# LogicBoard.net
KiCad netlist of a schematic drawn in EAGLE
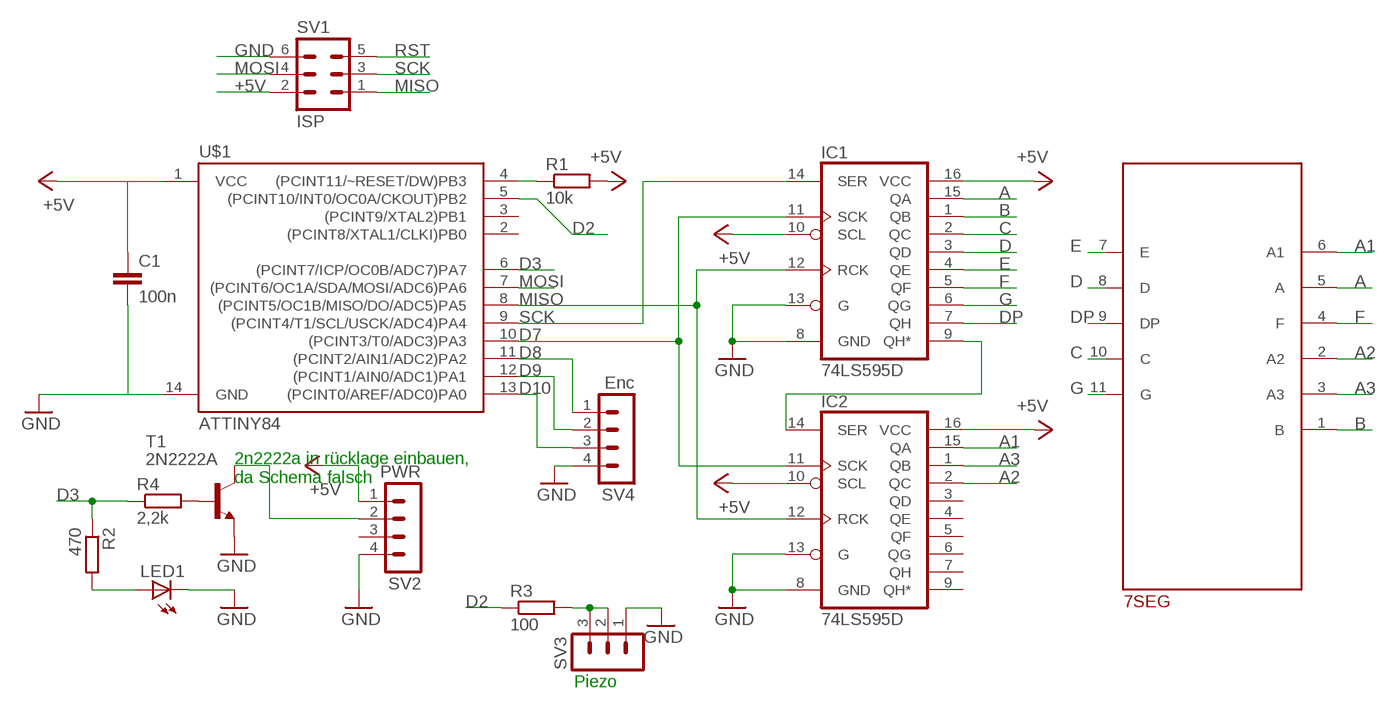
[diagram p0: schematic, sheet 1]

(export (version "E")
  (design (tool "Eeschema 10.0.6"))
  (components
    (comp (ref "7SEG")
      (value "TOT4301TOT-4301FG1")
      (footprint "eagle-import:TOT4301")
      (libsource (lib "eagle-import") (part "TOT4301TOT-4301FG1"))
    )
    (comp (ref "C1")
      (value "100n")
      (footprint "eagle-import:C0805")
      (libsource (lib "eagle-import") (part "C-EUC0805"))
    )
    (comp (ref "IC1")
      (value "74LS595D")
      (footprint "eagle-import:SO16")
      (libsource (lib "eagle-import") (part "74595DLS"))
    )
    (comp (ref "IC2")
      (value "74LS595D")
      (footprint "eagle-import:SO16")
      (libsource (lib "eagle-import") (part "74595DLS"))
    )
    (comp (ref "LED1")
      (value "LED5MM")
      (footprint "eagle-import:LED5MM")
      (libsource (lib "eagle-import") (part "LED5MM"))
    )
    (comp (ref "R1")
      (value "10k")
      (footprint "eagle-import:M0805")
      (libsource (lib "eagle-import") (part "R-EU_M0805"))
    )
    (comp (ref "R2")
      (value "470")
      (footprint "eagle-import:M0805")
      (libsource (lib "eagle-import") (part "R-EU_M0805"))
    )
    (comp (ref "R3")
      (value "100")
      (footprint "eagle-import:M0805")
      (libsource (lib "eagle-import") (part "R-EU_M0805"))
    )
    (comp (ref "R4")
      (value "2,2k")
      (footprint "eagle-import:M0805")
      (libsource (lib "eagle-import") (part "R-EU_M0805"))
    )
    (comp (ref "SV1")
      (value "ISP")
      (footprint "eagle-import:MA03-2")
      (libsource (lib "eagle-import") (part "MA03-2"))
    )
    (comp (ref "SV2")
      (value "PWR")
      (footprint "eagle-import:MA04-1")
      (libsource (lib "eagle-import") (part "MA04-1"))
    )
    (comp (ref "SV3")
      (value "MA03-1")
      (footprint "eagle-import:MA03-1")
      (libsource (lib "eagle-import") (part "MA03-1"))
    )
    (comp (ref "SV4")
      (value "Enc")
      (footprint "eagle-import:MA04-1")
      (libsource (lib "eagle-import") (part "MA04-1"))
    )
    (comp (ref "T1")
      (value "2N2222A")
      (footprint "eagle-import:SOT23-EBC")
      (libsource (lib "eagle-import") (part "-NPN-SOT23-EBC"))
    )
    (comp (ref "U$1")
      (value "ATTINY84")
      (footprint "eagle-import:SO14")
      (libsource (lib "eagle-import") (part "ATTINY84"))
    )
  )
  (nets
    (net (code "1") (name "+5V") (class "Default")
      (node (ref "C1") (pin "1") (pinfunction "1_1") (pintype "passive"))
      (node (ref "IC1") (pin "10") (pinfunction "SCL_10") (pintype "input"))
      (node (ref "IC1") (pin "16") (pinfunction "VCC_16") (pintype "power_in"))
      (node (ref "IC2") (pin "10") (pinfunction "SCL_10") (pintype "input"))
      (node (ref "IC2") (pin "16") (pinfunction "VCC_16") (pintype "power_in"))
      (node (ref "R1") (pin "2") (pinfunction "2_2") (pintype "passive"))
      (node (ref "SV1") (pin "2") (pinfunction "2_2") (pintype "passive"))
      (node (ref "SV2") (pin "1") (pinfunction "1_1") (pintype "passive"))
      (node (ref "U$1") (pin "1") (pinfunction "VCC_1") (pintype "bidirectional"))
    )
    (net (code "2") (name "/A") (class "Default")
      (node (ref "7SEG") (pin "5") (pinfunction "A_5") (pintype "bidirectional"))
      (node (ref "IC1") (pin "15") (pinfunction "QA_15") (pintype "tri_state"))
    )
    (net (code "3") (name "/A1") (class "Default")
      (node (ref "7SEG") (pin "6") (pinfunction "A1_6") (pintype "bidirectional"))
      (node (ref "IC2") (pin "15") (pinfunction "QA_15") (pintype "tri_state"))
    )
    (net (code "4") (name "/A2") (class "Default")
      (node (ref "7SEG") (pin "2") (pinfunction "A2_2") (pintype "bidirectional"))
      (node (ref "IC2") (pin "2") (pinfunction "QC_2") (pintype "tri_state"))
    )
    (net (code "5") (name "/A3") (class "Default")
      (node (ref "7SEG") (pin "3") (pinfunction "A3_3") (pintype "bidirectional"))
      (node (ref "IC2") (pin "1") (pinfunction "QB_1") (pintype "tri_state"))
    )
    (net (code "6") (name "/B") (class "Default")
      (node (ref "7SEG") (pin "1") (pinfunction "B_1") (pintype "bidirectional"))
      (node (ref "IC1") (pin "1") (pinfunction "QB_1") (pintype "tri_state"))
    )
    (net (code "7") (name "/C") (class "Default")
      (node (ref "7SEG") (pin "10") (pinfunction "C_10") (pintype "bidirectional"))
      (node (ref "IC1") (pin "2") (pinfunction "QC_2") (pintype "tri_state"))
    )
    (net (code "8") (name "/D") (class "Default")
      (node (ref "7SEG") (pin "8") (pinfunction "D_8") (pintype "bidirectional"))
      (node (ref "IC1") (pin "3") (pinfunction "QD_3") (pintype "tri_state"))
    )
    (net (code "9") (name "/D2") (class "Default")
      (node (ref "R3") (pin "1") (pinfunction "1_1") (pintype "passive"))
      (node (ref "U$1") (pin "5") (pinfunction "(PCINT10/INT0/OC0A/CKOUT)PB2_5") (pintype "bidirectional"))
    )
    (net (code "10") (name "/D3") (class "Default")
      (node (ref "R2") (pin "1") (pinfunction "1_1") (pintype "passive"))
      (node (ref "R4") (pin "1") (pinfunction "1_1") (pintype "passive"))
      (node (ref "U$1") (pin "6") (pinfunction "(PCINT7/ICP/OC0B/ADC7)PA7_6") (pintype "bidirectional"))
    )
    (net (code "11") (name "/D7") (class "Default")
      (node (ref "IC1") (pin "11") (pinfunction "SCK_11") (pintype "input"))
      (node (ref "IC2") (pin "11") (pinfunction "SCK_11") (pintype "input"))
      (node (ref "U$1") (pin "10") (pinfunction "(PCINT3/T0/ADC3)PA3_10") (pintype "bidirectional"))
    )
    (net (code "12") (name "/D8") (class "Default")
      (node (ref "SV4") (pin "1") (pinfunction "1_1") (pintype "passive"))
      (node (ref "U$1") (pin "11") (pinfunction "(PCINT2/AIN1/ADC2)PA2_11") (pintype "bidirectional"))
    )
    (net (code "13") (name "/D9") (class "Default")
      (node (ref "SV4") (pin "2") (pinfunction "2_2") (pintype "passive"))
      (node (ref "U$1") (pin "12") (pinfunction "(PCINT1/AIN0/ADC1)PA1_12") (pintype "bidirectional"))
    )
    (net (code "14") (name "/D10") (class "Default")
      (node (ref "SV4") (pin "3") (pinfunction "3_3") (pintype "passive"))
      (node (ref "U$1") (pin "13") (pinfunction "(PCINT0/AREF/ADC0)PA0_13") (pintype "bidirectional"))
    )
    (net (code "15") (name "/DP") (class "Default")
      (node (ref "7SEG") (pin "9") (pinfunction "DP_9") (pintype "bidirectional"))
      (node (ref "IC1") (pin "7") (pinfunction "QH_7") (pintype "tri_state"))
    )
    (net (code "16") (name "/E") (class "Default")
      (node (ref "7SEG") (pin "7") (pinfunction "E_7") (pintype "bidirectional"))
      (node (ref "IC1") (pin "4") (pinfunction "QE_4") (pintype "tri_state"))
    )
    (net (code "17") (name "/F") (class "Default")
      (node (ref "7SEG") (pin "4") (pinfunction "F_4") (pintype "bidirectional"))
      (node (ref "IC1") (pin "5") (pinfunction "QF_5") (pintype "tri_state"))
    )
    (net (code "18") (name "/G") (class "Default")
      (node (ref "7SEG") (pin "11") (pinfunction "G_11") (pintype "bidirectional"))
      (node (ref "IC1") (pin "6") (pinfunction "QG_6") (pintype "tri_state"))
    )
    (net (code "19") (name "/MISO") (class "Default")
      (node (ref "IC1") (pin "12") (pinfunction "RCK_12") (pintype "input"))
      (node (ref "IC2") (pin "12") (pinfunction "RCK_12") (pintype "input"))
      (node (ref "SV1") (pin "1") (pinfunction "1_1") (pintype "passive"))
      (node (ref "U$1") (pin "8") (pinfunction "(PCINT5/OC1B/MISO/DO/ADC5)PA5_8") (pintype "bidirectional"))
    )
    (net (code "20") (name "/MOSI") (class "Default")
      (node (ref "SV1") (pin "4") (pinfunction "4_4") (pintype "passive"))
      (node (ref "U$1") (pin "7") (pinfunction "(PCINT6/OC1A/SDA/MOSI/ADC6)PA6_7") (pintype "bidirectional"))
    )
    (net (code "21") (name "/RST") (class "Default")
      (node (ref "R1") (pin "1") (pinfunction "1_1") (pintype "passive"))
      (node (ref "SV1") (pin "5") (pinfunction "5_5") (pintype "passive"))
      (node (ref "U$1") (pin "4") (pinfunction "(PCINT11/~{RESET/DW})PB3_4") (pintype "bidirectional"))
    )
    (net (code "22") (name "/SCK") (class "Default")
      (node (ref "IC1") (pin "14") (pinfunction "SER_14") (pintype "input"))
      (node (ref "SV1") (pin "3") (pinfunction "3_3") (pintype "passive"))
      (node (ref "U$1") (pin "9") (pinfunction "(PCINT4/T1/SCL/USCK/ADC4)PA4_9") (pintype "bidirectional"))
    )
    (net (code "23") (name "GND") (class "Default")
      (node (ref "C1") (pin "2") (pinfunction "2_2") (pintype "passive"))
      (node (ref "IC1") (pin "13") (pinfunction "G_13") (pintype "input"))
      (node (ref "IC1") (pin "8") (pinfunction "GND_8") (pintype "power_in"))
      (node (ref "IC2") (pin "13") (pinfunction "G_13") (pintype "input"))
      (node (ref "IC2") (pin "8") (pinfunction "GND_8") (pintype "power_in"))
      (node (ref "LED1") (pin "K") (pinfunction "C_K") (pintype "passive"))
      (node (ref "SV1") (pin "6") (pinfunction "6_6") (pintype "passive"))
      (node (ref "SV2") (pin "4") (pinfunction "4_4") (pintype "passive"))
      (node (ref "SV3") (pin "1") (pinfunction "1_1") (pintype "passive"))
      (node (ref "SV4") (pin "4") (pinfunction "4_4") (pintype "passive"))
      (node (ref "T1") (pin "E") (pinfunction "E_E") (pintype "passive"))
      (node (ref "U$1") (pin "14") (pinfunction "GND_14") (pintype "bidirectional"))
    )
    (net (code "24") (name "Net-(IC1-QH*)") (class "Default")
      (node (ref "IC1") (pin "9") (pinfunction "QH*_9") (pintype "tri_state"))
      (node (ref "IC2") (pin "14") (pinfunction "SER_14") (pintype "input"))
    )
    (net (code "25") (name "Net-(LED1-PadA)") (class "Default")
      (node (ref "LED1") (pin "A") (pinfunction "A_A") (pintype "passive"))
      (node (ref "R2") (pin "2") (pinfunction "2_2") (pintype "passive"))
    )
    (net (code "26") (name "Net-(R3-Pad2)") (class "Default")
      (node (ref "R3") (pin "2") (pinfunction "2_2") (pintype "passive"))
      (node (ref "SV3") (pin "2") (pinfunction "2_2") (pintype "passive"))
      (node (ref "SV3") (pin "3") (pinfunction "3_3") (pintype "passive"))
    )
    (net (code "27") (name "Net-(R4-Pad2)") (class "Default")
      (node (ref "R4") (pin "2") (pinfunction "2_2") (pintype "passive"))
      (node (ref "T1") (pin "B") (pinfunction "B_B") (pintype "passive"))
    )
    (net (code "28") (name "Net-(SV2-Pad2)") (class "Default")
      (node (ref "SV2") (pin "2") (pinfunction "2_2") (pintype "passive"))
      (node (ref "T1") (pin "C") (pinfunction "C_C") (pintype "passive"))
    )
    (net (code "29") (name "unconnected-(IC2-QD-Pad3)") (class "Default")
      (node (ref "IC2") (pin "3") (pinfunction "QD_3") (pintype "tri_state"))
    )
    (net (code "30") (name "unconnected-(IC2-QE-Pad4)") (class "Default")
      (node (ref "IC2") (pin "4") (pinfunction "QE_4") (pintype "tri_state"))
    )
    (net (code "31") (name "unconnected-(IC2-QF-Pad5)") (class "Default")
      (node (ref "IC2") (pin "5") (pinfunction "QF_5") (pintype "tri_state"))
    )
    (net (code "32") (name "unconnected-(IC2-QG-Pad6)") (class "Default")
      (node (ref "IC2") (pin "6") (pinfunction "QG_6") (pintype "tri_state"))
    )
    (net (code "33") (name "unconnected-(IC2-QH*-Pad9)") (class "Default")
      (node (ref "IC2") (pin "9") (pinfunction "QH*_9") (pintype "tri_state"))
    )
    (net (code "34") (name "unconnected-(IC2-QH-Pad7)") (class "Default")
      (node (ref "IC2") (pin "7") (pinfunction "QH_7") (pintype "tri_state"))
    )
    (net (code "35") (name "unconnected-(SV2-Pad3)") (class "Default")
      (node (ref "SV2") (pin "3") (pinfunction "3_3") (pintype "passive"))
    )
    (net (code "36") (name "unconnected-(U$1-(PCINT8{slash}XTAL1{slash}CLKI)PB0-Pad2)") (class "Default")
      (node (ref "U$1") (pin "2") (pinfunction "(PCINT8/XTAL1/CLKI)PB0_2") (pintype "bidirectional"))
    )
    (net (code "37") (name "unconnected-(U$1-(PCINT9{slash}XTAL2)PB1-Pad3)") (class "Default")
      (node (ref "U$1") (pin "3") (pinfunction "(PCINT9/XTAL2)PB1_3") (pintype "bidirectional"))
    )
  )
)
